# IRreceiver.net
KiCad netlist of a schematic drawn in EAGLE
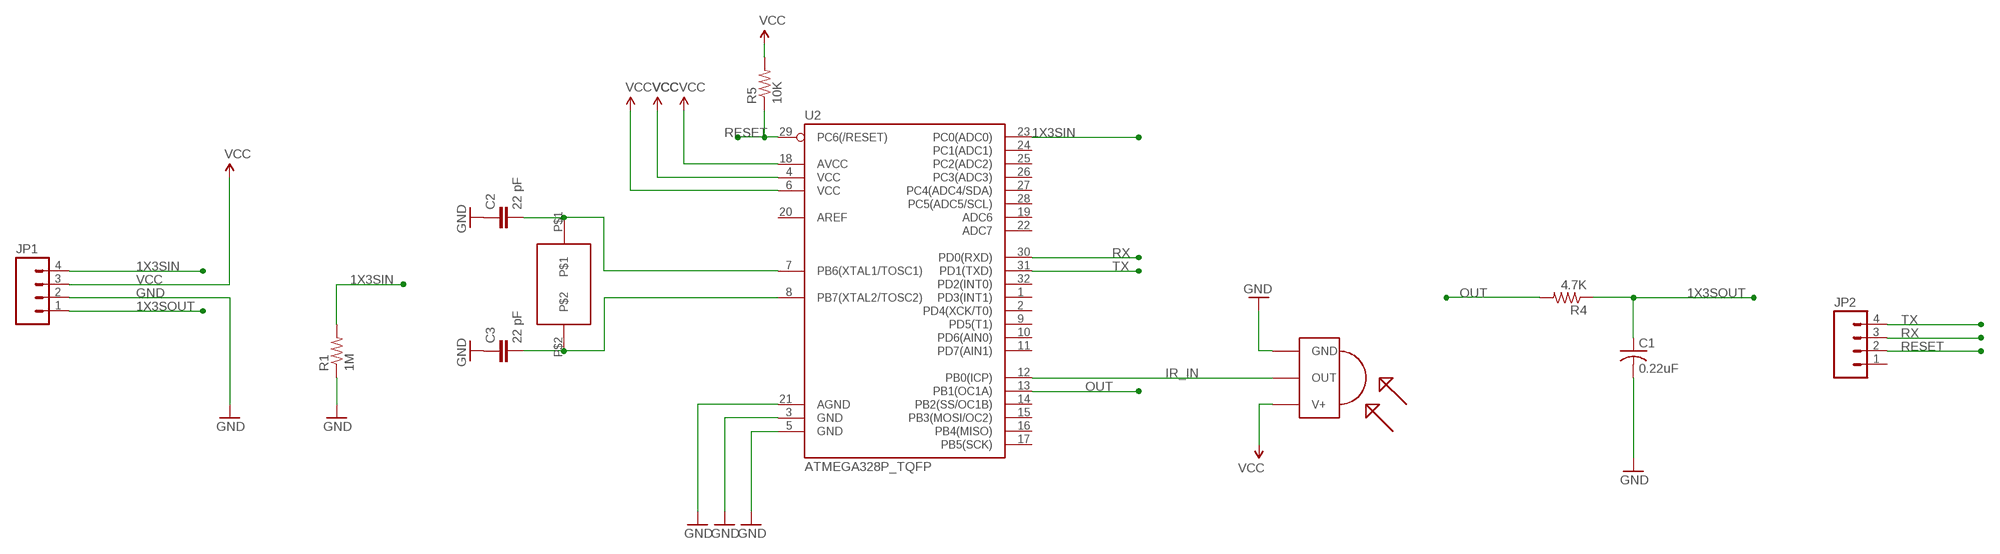
[diagram p0: schematic, sheet 1]

(export (version "E")
  (design (tool "Eeschema 10.0.6"))
  (components
    (comp (ref "C1")
      (value "0.22uF")
      (footprint "eagle-import:C0402")
      (libsource (lib "eagle-import") (part "C-USC0402"))
    )
    (comp (ref "C2")
      (value "22 pF")
      (footprint "eagle-import:0603-CAP")
      (libsource (lib "eagle-import") (part "CAP0603-CAP"))
    )
    (comp (ref "C3")
      (value "22 pF")
      (footprint "eagle-import:0603-CAP")
      (libsource (lib "eagle-import") (part "CAP0603-CAP"))
    )
    (comp (ref "JP1")
      (value "M04PTH")
      (footprint "eagle-import:1X04")
      (libsource (lib "eagle-import") (part "M04PTH"))
    )
    (comp (ref "JP2")
      (value "M04PTH")
      (footprint "eagle-import:1X04")
      (libsource (lib "eagle-import") (part "M04PTH"))
    )
    (comp (ref "R1")
      (value "1M")
      (footprint "eagle-import:R0603")
      (libsource (lib "eagle-import") (part "R-US_R0603"))
    )
    (comp (ref "R4")
      (value "4.7K")
      (footprint "eagle-import:R0603")
      (libsource (lib "eagle-import") (part "R-US_R0603"))
    )
    (comp (ref "R5")
      (value "10K")
      (footprint "eagle-import:R0603")
      (libsource (lib "eagle-import") (part "resistor_R-US_R0603"))
    )
    (comp (ref "U$1")
      (value "TSOP38238")
      (footprint "eagle-import:TSOP382XX,384XX")
      (libsource (lib "eagle-import") (part "TSOP38238"))
    )
    (comp (ref "U$2")
      (value "NX503")
      (footprint "eagle-import:NX503")
      (libsource (lib "eagle-import") (part "NX503"))
    )
    (comp (ref "U2")
      (value "ATMEGA328P_TQFP")
      (footprint "eagle-import:TQFP32-08")
      (libsource (lib "eagle-import") (part "ATMEGA328P_TQFP"))
    )
  )
  (nets
    (net (code "1") (name "/1X3SIN") (class "Default")
      (node (ref "JP1") (pin "4") (pinfunction "4_4") (pintype "passive"))
      (node (ref "R1") (pin "2") (pinfunction "2_2") (pintype "passive"))
      (node (ref "U2") (pin "23") (pinfunction "PC0(ADC0)_23") (pintype "bidirectional"))
    )
    (net (code "2") (name "/1X3SOUT") (class "Default")
      (node (ref "C1") (pin "1") (pinfunction "1_1") (pintype "passive"))
      (node (ref "JP1") (pin "1") (pinfunction "1_1") (pintype "passive"))
      (node (ref "R4") (pin "1") (pinfunction "1_1") (pintype "passive"))
    )
    (net (code "3") (name "/IR_IN") (class "Default")
      (node (ref "U$1") (pin "OUT") (pinfunction "OUT_OUT") (pintype "bidirectional"))
      (node (ref "U2") (pin "12") (pinfunction "PB0(ICP)_12") (pintype "bidirectional"))
    )
    (net (code "4") (name "/OUT") (class "Default")
      (node (ref "R4") (pin "2") (pinfunction "2_2") (pintype "passive"))
      (node (ref "U2") (pin "13") (pinfunction "PB1(OC1A)_13") (pintype "bidirectional"))
    )
    (net (code "5") (name "/RESET") (class "Default")
      (node (ref "JP2") (pin "2") (pinfunction "2_2") (pintype "passive"))
      (node (ref "R5") (pin "1") (pinfunction "1_1") (pintype "passive"))
      (node (ref "U2") (pin "29") (pinfunction "PC6(/RESET)_29") (pintype "bidirectional"))
    )
    (net (code "6") (name "/RX") (class "Default")
      (node (ref "JP2") (pin "3") (pinfunction "3_3") (pintype "passive"))
      (node (ref "U2") (pin "30") (pinfunction "PD0(RXD)_30") (pintype "bidirectional"))
    )
    (net (code "7") (name "/TX") (class "Default")
      (node (ref "JP2") (pin "4") (pinfunction "4_4") (pintype "passive"))
      (node (ref "U2") (pin "31") (pinfunction "PD1(TXD)_31") (pintype "bidirectional"))
    )
    (net (code "8") (name "GND") (class "Default")
      (node (ref "C1") (pin "2") (pinfunction "2_2") (pintype "passive"))
      (node (ref "C2") (pin "1") (pinfunction "1_1") (pintype "passive"))
      (node (ref "C3") (pin "1") (pinfunction "1_1") (pintype "passive"))
      (node (ref "JP1") (pin "2") (pinfunction "2_2") (pintype "passive"))
      (node (ref "R1") (pin "1") (pinfunction "1_1") (pintype "passive"))
      (node (ref "U$1") (pin "GND") (pinfunction "GND_GND") (pintype "bidirectional"))
      (node (ref "U2") (pin "21") (pinfunction "AGND_21") (pintype "bidirectional"))
      (node (ref "U2") (pin "3") (pinfunction "GND_3") (pintype "bidirectional"))
      (node (ref "U2") (pin "5") (pinfunction "GND_5") (pintype "bidirectional"))
    )
    (net (code "9") (name "Net-(U2-PB6(XTAL1{slash}TOSC1))") (class "Default")
      (node (ref "C2") (pin "2") (pinfunction "2_2") (pintype "passive"))
      (node (ref "U$2") (pin "P$1") (pinfunction "P$1_P$1") (pintype "bidirectional"))
      (node (ref "U2") (pin "7") (pinfunction "PB6(XTAL1/TOSC1)_7") (pintype "bidirectional"))
    )
    (net (code "10") (name "Net-(U2-PB7(XTAL2{slash}TOSC2))") (class "Default")
      (node (ref "C3") (pin "2") (pinfunction "2_2") (pintype "passive"))
      (node (ref "U$2") (pin "P$2") (pinfunction "P$2_P$2") (pintype "bidirectional"))
      (node (ref "U2") (pin "8") (pinfunction "PB7(XTAL2/TOSC2)_8") (pintype "bidirectional"))
    )
    (net (code "11") (name "VCC") (class "Default")
      (node (ref "JP1") (pin "3") (pinfunction "3_3") (pintype "passive"))
      (node (ref "R5") (pin "2") (pinfunction "2_2") (pintype "passive"))
      (node (ref "U$1") (pin "VS") (pinfunction "V+_VS") (pintype "bidirectional"))
      (node (ref "U2") (pin "18") (pinfunction "AVCC_18") (pintype "bidirectional"))
      (node (ref "U2") (pin "4") (pinfunction "VCC_4") (pintype "bidirectional"))
      (node (ref "U2") (pin "6") (pinfunction "VCC_6") (pintype "bidirectional"))
    )
    (net (code "12") (name "unconnected-(JP2-Pad1)") (class "Default")
      (node (ref "JP2") (pin "1") (pinfunction "1_1") (pintype "passive"))
    )
    (net (code "13") (name "unconnected-(U2-ADC6-Pad19)") (class "Default")
      (node (ref "U2") (pin "19") (pinfunction "ADC6_19") (pintype "bidirectional"))
    )
    (net (code "14") (name "unconnected-(U2-ADC7-Pad22)") (class "Default")
      (node (ref "U2") (pin "22") (pinfunction "ADC7_22") (pintype "bidirectional"))
    )
    (net (code "15") (name "unconnected-(U2-AREF-Pad20)") (class "Default")
      (node (ref "U2") (pin "20") (pinfunction "AREF_20") (pintype "bidirectional"))
    )
    (net (code "16") (name "unconnected-(U2-PB2(SS{slash}OC1B)-Pad14)") (class "Default")
      (node (ref "U2") (pin "14") (pinfunction "PB2(SS/OC1B)_14") (pintype "bidirectional"))
    )
    (net (code "17") (name "unconnected-(U2-PB3(MOSI{slash}OC2)-Pad15)") (class "Default")
      (node (ref "U2") (pin "15") (pinfunction "PB3(MOSI/OC2)_15") (pintype "bidirectional"))
    )
    (net (code "18") (name "unconnected-(U2-PB4(MISO)-Pad16)") (class "Default")
      (node (ref "U2") (pin "16") (pinfunction "PB4(MISO)_16") (pintype "bidirectional"))
    )
    (net (code "19") (name "unconnected-(U2-PB5(SCK)-Pad17)") (class "Default")
      (node (ref "U2") (pin "17") (pinfunction "PB5(SCK)_17") (pintype "bidirectional"))
    )
    (net (code "20") (name "unconnected-(U2-PC1(ADC1)-Pad24)") (class "Default")
      (node (ref "U2") (pin "24") (pinfunction "PC1(ADC1)_24") (pintype "bidirectional"))
    )
    (net (code "21") (name "unconnected-(U2-PC2(ADC2)-Pad25)") (class "Default")
      (node (ref "U2") (pin "25") (pinfunction "PC2(ADC2)_25") (pintype "bidirectional"))
    )
    (net (code "22") (name "unconnected-(U2-PC3(ADC3)-Pad26)") (class "Default")
      (node (ref "U2") (pin "26") (pinfunction "PC3(ADC3)_26") (pintype "bidirectional"))
    )
    (net (code "23") (name "unconnected-(U2-PC4(ADC4{slash}SDA)-Pad27)") (class "Default")
      (node (ref "U2") (pin "27") (pinfunction "PC4(ADC4/SDA)_27") (pintype "bidirectional"))
    )
    (net (code "24") (name "unconnected-(U2-PC5(ADC5{slash}SCL)-Pad28)") (class "Default")
      (node (ref "U2") (pin "28") (pinfunction "PC5(ADC5/SCL)_28") (pintype "bidirectional"))
    )
    (net (code "25") (name "unconnected-(U2-PD2(INT0)-Pad32)") (class "Default")
      (node (ref "U2") (pin "32") (pinfunction "PD2(INT0)_32") (pintype "bidirectional"))
    )
    (net (code "26") (name "unconnected-(U2-PD3(INT1)-Pad1)") (class "Default")
      (node (ref "U2") (pin "1") (pinfunction "PD3(INT1)_1") (pintype "bidirectional"))
    )
    (net (code "27") (name "unconnected-(U2-PD4(XCK{slash}T0)-Pad2)") (class "Default")
      (node (ref "U2") (pin "2") (pinfunction "PD4(XCK/T0)_2") (pintype "bidirectional"))
    )
    (net (code "28") (name "unconnected-(U2-PD5(T1)-Pad9)") (class "Default")
      (node (ref "U2") (pin "9") (pinfunction "PD5(T1)_9") (pintype "bidirectional"))
    )
    (net (code "29") (name "unconnected-(U2-PD6(AIN0)-Pad10)") (class "Default")
      (node (ref "U2") (pin "10") (pinfunction "PD6(AIN0)_10") (pintype "bidirectional"))
    )
    (net (code "30") (name "unconnected-(U2-PD7(AIN1)-Pad11)") (class "Default")
      (node (ref "U2") (pin "11") (pinfunction "PD7(AIN1)_11") (pintype "bidirectional"))
    )
  )
)
